# od2.net
KiCad netlist of a schematic drawn in EAGLE
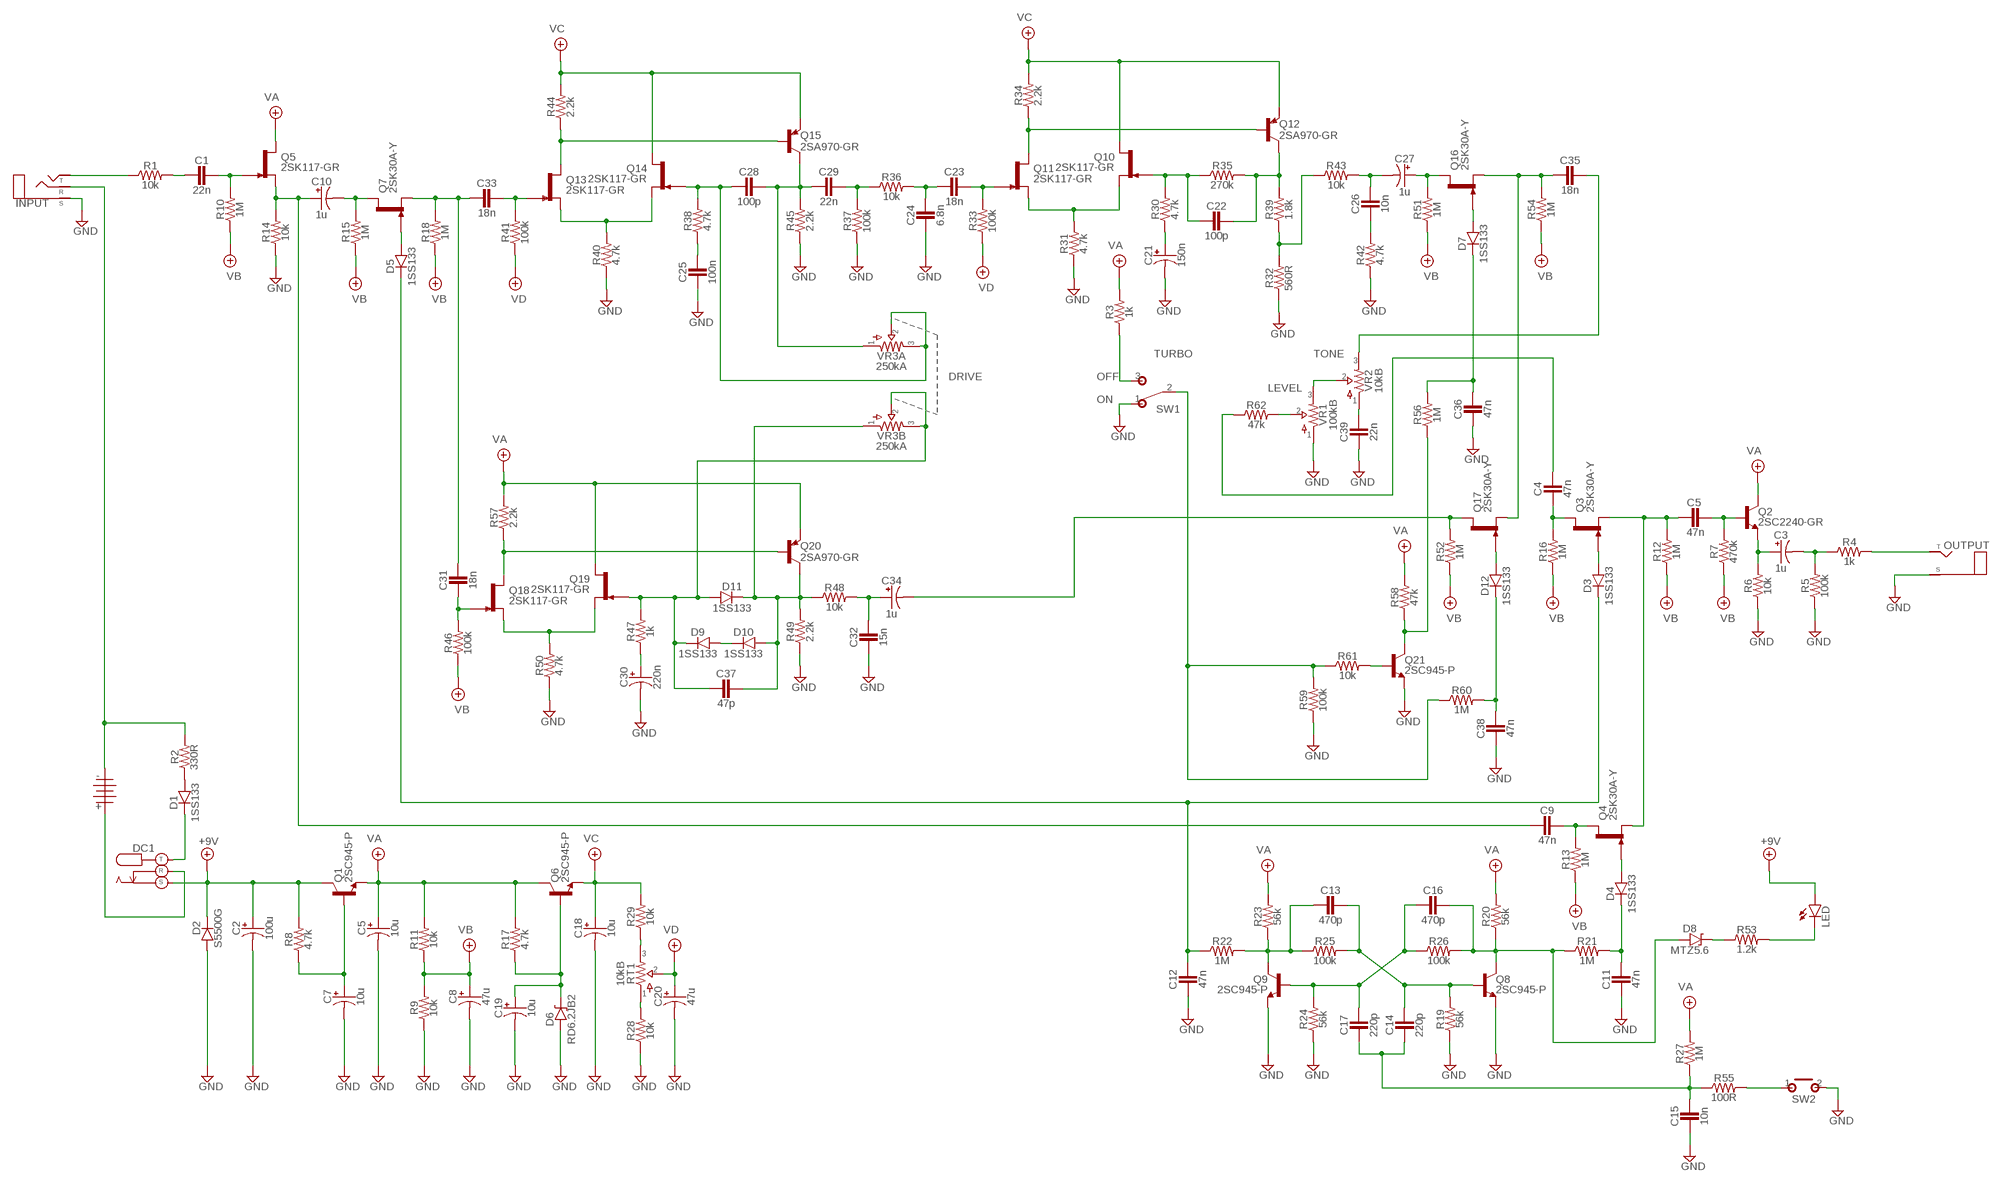
[diagram p0: schematic, sheet 1]

(export (version "E")
  (design (tool "Eeschema 10.0.6"))
  (components
    (comp (ref "11")
      (value "BATTERY")
      (footprint "eagle-import:TWO_PADS")
      (libsource (lib "eagle-import") (part "BATTERY"))
    )
    (comp (ref "C1")
      (value "22n")
      (footprint "eagle-import:BOX_SMALL")
      (libsource (lib "eagle-import") (part "CER/FILMBOX.1"))
    )
    (comp (ref "C2")
      (value "100u")
      (footprint "eagle-import:040_020")
      (libsource (lib "eagle-import") (part "0400"))
    )
    (comp (ref "C3")
      (value "1u")
      (footprint "eagle-import:040_020")
      (libsource (lib "eagle-import") (part "0400"))
    )
    (comp (ref "C4")
      (value "47n")
      (footprint "eagle-import:BOX_SMALL")
      (libsource (lib "eagle-import") (part "CER/FILMBOX.1"))
    )
    (comp (ref "C5")
      (value "10u")
      (footprint "eagle-import:040_020")
      (libsource (lib "eagle-import") (part "0400"))
    )
    (comp (ref "C5 ")
      (value "47n")
      (footprint "eagle-import:BOX_SMALL")
      (libsource (lib "eagle-import") (part "CER/FILMBOX.1"))
    )
    (comp (ref "C7")
      (value "10u")
      (footprint "eagle-import:040_020")
      (libsource (lib "eagle-import") (part "0400"))
    )
    (comp (ref "C8")
      (value "47u")
      (footprint "eagle-import:040_020")
      (libsource (lib "eagle-import") (part "0400"))
    )
    (comp (ref "C9")
      (value "47n")
      (footprint "eagle-import:BOX_SMALL")
      (libsource (lib "eagle-import") (part "CER/FILMBOX.1"))
    )
    (comp (ref "C10")
      (value "1u")
      (footprint "eagle-import:040_020")
      (libsource (lib "eagle-import") (part "0400"))
    )
    (comp (ref "C11")
      (value "47n")
      (footprint "eagle-import:BOX_SMALL")
      (libsource (lib "eagle-import") (part "CER/FILMBOX.1"))
    )
    (comp (ref "C12")
      (value "47n")
      (footprint "eagle-import:BOX_SMALL")
      (libsource (lib "eagle-import") (part "CER/FILMBOX.1"))
    )
    (comp (ref "C13")
      (value "470p")
      (footprint "eagle-import:BOX_SMALL")
      (libsource (lib "eagle-import") (part "CER/FILMBOX.1"))
    )
    (comp (ref "C14")
      (value "220p")
      (footprint "eagle-import:BOX_SMALL")
      (libsource (lib "eagle-import") (part "CER/FILMBOX.1"))
    )
    (comp (ref "C15")
      (value "10n")
      (footprint "eagle-import:BOX_SMALL")
      (libsource (lib "eagle-import") (part "CER/FILMBOX.1"))
    )
    (comp (ref "C16")
      (value "470p")
      (footprint "eagle-import:BOX_SMALL")
      (libsource (lib "eagle-import") (part "CER/FILMBOX.1"))
    )
    (comp (ref "C17")
      (value "220p")
      (footprint "eagle-import:BOX_SMALL")
      (libsource (lib "eagle-import") (part "CER/FILMBOX.1"))
    )
    (comp (ref "C18")
      (value "10u")
      (footprint "eagle-import:040_020")
      (libsource (lib "eagle-import") (part "0400"))
    )
    (comp (ref "C19")
      (value "10u")
      (footprint "eagle-import:040_020")
      (libsource (lib "eagle-import") (part "0400"))
    )
    (comp (ref "C20")
      (value "47u")
      (footprint "eagle-import:040_020")
      (libsource (lib "eagle-import") (part "0400"))
    )
    (comp (ref "C21")
      (value "150n")
      (footprint "eagle-import:040_020")
      (libsource (lib "eagle-import") (part "0400"))
    )
    (comp (ref "C22")
      (value "100p")
      (footprint "eagle-import:BOX_SMALL")
      (libsource (lib "eagle-import") (part "CER/FILMBOX.1"))
    )
    (comp (ref "C23")
      (value "18n")
      (footprint "eagle-import:BOX_SMALL")
      (libsource (lib "eagle-import") (part "CER/FILMBOX.1"))
    )
    (comp (ref "C24")
      (value "6.8n")
      (footprint "eagle-import:BOX_SMALL")
      (libsource (lib "eagle-import") (part "CER/FILMBOX.1"))
    )
    (comp (ref "C25")
      (value "100n")
      (footprint "eagle-import:BOX_SMALL")
      (libsource (lib "eagle-import") (part "CER/FILMBOX.1"))
    )
    (comp (ref "C26")
      (value "10n")
      (footprint "eagle-import:BOX_SMALL")
      (libsource (lib "eagle-import") (part "CER/FILMBOX.1"))
    )
    (comp (ref "C27")
      (value "1u")
      (footprint "eagle-import:040_020")
      (libsource (lib "eagle-import") (part "0400"))
    )
    (comp (ref "C28")
      (value "100p")
      (footprint "eagle-import:BOX_SMALL")
      (libsource (lib "eagle-import") (part "CER/FILMBOX.1"))
    )
    (comp (ref "C29")
      (value "22n")
      (footprint "eagle-import:BOX_SMALL")
      (libsource (lib "eagle-import") (part "CER/FILMBOX.1"))
    )
    (comp (ref "C30")
      (value "220n")
      (footprint "eagle-import:040_020")
      (libsource (lib "eagle-import") (part "0400"))
    )
    (comp (ref "C31")
      (value "18n")
      (footprint "eagle-import:BOX_SMALL")
      (libsource (lib "eagle-import") (part "CER/FILMBOX.1"))
    )
    (comp (ref "C32")
      (value "15n")
      (footprint "eagle-import:BOX_SMALL")
      (libsource (lib "eagle-import") (part "CER/FILMBOX.1"))
    )
    (comp (ref "C33")
      (value "18n")
      (footprint "eagle-import:BOX_SMALL")
      (libsource (lib "eagle-import") (part "CER/FILMBOX.1"))
    )
    (comp (ref "C34")
      (value "1u")
      (footprint "eagle-import:040_020")
      (libsource (lib "eagle-import") (part "0400"))
    )
    (comp (ref "C35")
      (value "18n")
      (footprint "eagle-import:BOX_SMALL")
      (libsource (lib "eagle-import") (part "CER/FILMBOX.1"))
    )
    (comp (ref "C36")
      (value "47n")
      (footprint "eagle-import:BOX_SMALL")
      (libsource (lib "eagle-import") (part "CER/FILMBOX.1"))
    )
    (comp (ref "C37")
      (value "47p")
      (footprint "eagle-import:BOX_SMALL")
      (libsource (lib "eagle-import") (part "CER/FILMBOX.1"))
    )
    (comp (ref "C38")
      (value "47n")
      (footprint "eagle-import:BOX_SMALL")
      (libsource (lib "eagle-import") (part "CER/FILMBOX.1"))
    )
    (comp (ref "C39")
      (value "22n")
      (footprint "eagle-import:BOX_SMALL")
      (libsource (lib "eagle-import") (part "CER/FILMBOX.1"))
    )
    (comp (ref "D1")
      (value "1SS133")
      (footprint "eagle-import:DO35-2")
      (libsource (lib "eagle-import") (part "DO35.2"))
    )
    (comp (ref "D2")
      (value "S5500G")
      (footprint "eagle-import:DO35-2")
      (libsource (lib "eagle-import") (part "DO35.2"))
    )
    (comp (ref "D3")
      (value "1SS133")
      (footprint "eagle-import:DO35-2")
      (libsource (lib "eagle-import") (part "DO35.2"))
    )
    (comp (ref "D4")
      (value "1SS133")
      (footprint "eagle-import:DO35-2")
      (libsource (lib "eagle-import") (part "DO35.2"))
    )
    (comp (ref "D5")
      (value "1SS133")
      (footprint "eagle-import:DO35-2")
      (libsource (lib "eagle-import") (part "DO35.2"))
    )
    (comp (ref "D6")
      (value "RD6.2JB2")
      (footprint "eagle-import:DO41-2")
      (libsource (lib "eagle-import") (part "ZENER.2"))
    )
    (comp (ref "D7")
      (value "1SS133")
      (footprint "eagle-import:DO35-2")
      (libsource (lib "eagle-import") (part "DO35.2"))
    )
    (comp (ref "D8")
      (value "MTZ5.6")
      (footprint "eagle-import:DO41-2")
      (libsource (lib "eagle-import") (part "ZENER.2"))
    )
    (comp (ref "D9")
      (value "1SS133")
      (footprint "eagle-import:DO35-2")
      (libsource (lib "eagle-import") (part "DO35.2"))
    )
    (comp (ref "D10")
      (value "1SS133")
      (footprint "eagle-import:DO35-2")
      (libsource (lib "eagle-import") (part "DO35.2"))
    )
    (comp (ref "D11")
      (value "1SS133")
      (footprint "eagle-import:DO35-2")
      (libsource (lib "eagle-import") (part "DO35.2"))
    )
    (comp (ref "D12")
      (value "1SS133")
      (footprint "eagle-import:DO35-2")
      (libsource (lib "eagle-import") (part "DO35.2"))
    )
    (comp (ref "DC1")
      (value "DC_KOBICONN")
      (footprint "eagle-import:DC_KOBICONN")
      (libsource (lib "eagle-import") (part "DC_KOBICONN"))
    )
    (comp (ref "INPUT")
      (value "STEREO3PADS")
      (footprint "eagle-import:THREEPADS")
      (libsource (lib "eagle-import") (part "STEREO3PADS"))
    )
    (comp (ref "LED")
      (value "LED")
      (footprint "eagle-import:3MM_D")
      (libsource (lib "eagle-import") (part "LED"))
    )
    (comp (ref "OUTPUT")
      (value "MONO")
      (footprint "eagle-import:TWO_PADS")
      (libsource (lib "eagle-import") (part "MONO"))
    )
    (comp (ref "Q1")
      (value "2SC945-P")
      (footprint "eagle-import:TO92-")
      (libsource (lib "eagle-import") (part "2SC828A"))
    )
    (comp (ref "Q2")
      (value "2SC2240-GR")
      (footprint "eagle-import:TO92-")
      (libsource (lib "eagle-import") (part "2SC828A"))
    )
    (comp (ref "Q3")
      (value "2SK30A-Y")
      (footprint "eagle-import:TO92-")
      (libsource (lib "eagle-import") (part "2N3819TO-92S"))
    )
    (comp (ref "Q4")
      (value "2SK30A-Y")
      (footprint "eagle-import:TO92-")
      (libsource (lib "eagle-import") (part "2N3819TO-92S"))
    )
    (comp (ref "Q5")
      (value "2SK117-GR")
      (footprint "eagle-import:TO92-")
      (libsource (lib "eagle-import") (part "2N3819TO-92S"))
    )
    (comp (ref "Q6")
      (value "2SC945-P")
      (footprint "eagle-import:TO92-")
      (libsource (lib "eagle-import") (part "2SC828A"))
    )
    (comp (ref "Q7")
      (value "2SK30A-Y")
      (footprint "eagle-import:TO92-")
      (libsource (lib "eagle-import") (part "2N3819TO-92S"))
    )
    (comp (ref "Q8")
      (value "2SC945-P")
      (footprint "eagle-import:TO92-")
      (libsource (lib "eagle-import") (part "2SC828A"))
    )
    (comp (ref "Q9")
      (value "2SC945-P")
      (footprint "eagle-import:TO92-")
      (libsource (lib "eagle-import") (part "2SC828A"))
    )
    (comp (ref "Q10")
      (value "2SK117-GR")
      (footprint "eagle-import:TO92-")
      (libsource (lib "eagle-import") (part "2N3819TO-92S"))
    )
    (comp (ref "Q11")
      (value "2SK117-GR")
      (footprint "eagle-import:TO92-")
      (libsource (lib "eagle-import") (part "2N3819TO-92S"))
    )
    (comp (ref "Q12")
      (value "2SA970-GR")
      (footprint "eagle-import:TO92")
      (libsource (lib "eagle-import") (part "2N3906"))
    )
    (comp (ref "Q13")
      (value "2SK117-GR")
      (footprint "eagle-import:TO92-")
      (libsource (lib "eagle-import") (part "2N3819TO-92S"))
    )
    (comp (ref "Q14")
      (value "2SK117-GR")
      (footprint "eagle-import:TO92-")
      (libsource (lib "eagle-import") (part "2N3819TO-92S"))
    )
    (comp (ref "Q15")
      (value "2SA970-GR")
      (footprint "eagle-import:TO92")
      (libsource (lib "eagle-import") (part "2N3906"))
    )
    (comp (ref "Q16")
      (value "2SK30A-Y")
      (footprint "eagle-import:TO92-")
      (libsource (lib "eagle-import") (part "2N3819TO-92S"))
    )
    (comp (ref "Q17")
      (value "2SK30A-Y")
      (footprint "eagle-import:TO92-")
      (libsource (lib "eagle-import") (part "2N3819TO-92S"))
    )
    (comp (ref "Q18")
      (value "2SK117-GR")
      (footprint "eagle-import:TO92-")
      (libsource (lib "eagle-import") (part "2N3819TO-92S"))
    )
    (comp (ref "Q19")
      (value "2SK117-GR")
      (footprint "eagle-import:TO92-")
      (libsource (lib "eagle-import") (part "2N3819TO-92S"))
    )
    (comp (ref "Q20")
      (value "2SA970-GR")
      (footprint "eagle-import:TO92")
      (libsource (lib "eagle-import") (part "2N3906"))
    )
    (comp (ref "Q21")
      (value "2SC945-P")
      (footprint "eagle-import:TO92-")
      (libsource (lib "eagle-import") (part "2SC828A"))
    )
    (comp (ref "R1")
      (value "10k")
      (footprint "eagle-import:R0207_3")
      (libsource (lib "eagle-import") (part "R_.3B"))
    )
    (comp (ref "R2")
      (value "330R")
      (footprint "eagle-import:R0207_3")
      (libsource (lib "eagle-import") (part "R_.3B"))
    )
    (comp (ref "R3")
      (value "1k")
      (footprint "eagle-import:R0207_3")
      (libsource (lib "eagle-import") (part "R_.3B"))
    )
    (comp (ref "R4")
      (value "1k")
      (footprint "eagle-import:R0207_3")
      (libsource (lib "eagle-import") (part "R_.3B"))
    )
    (comp (ref "R5")
      (value "100k")
      (footprint "eagle-import:R0207_3")
      (libsource (lib "eagle-import") (part "R_.3B"))
    )
    (comp (ref "R6")
      (value "10k")
      (footprint "eagle-import:R0207_3")
      (libsource (lib "eagle-import") (part "R_.3B"))
    )
    (comp (ref "R7")
      (value "470k")
      (footprint "eagle-import:R0207_3")
      (libsource (lib "eagle-import") (part "R_.3B"))
    )
    (comp (ref "R8")
      (value "4.7k")
      (footprint "eagle-import:R0207_3")
      (libsource (lib "eagle-import") (part "R_.3B"))
    )
    (comp (ref "R9")
      (value "10k")
      (footprint "eagle-import:R0207_3")
      (libsource (lib "eagle-import") (part "R_.3B"))
    )
    (comp (ref "R10")
      (value "1M")
      (footprint "eagle-import:R0207_3")
      (libsource (lib "eagle-import") (part "R_.3B"))
    )
    (comp (ref "R11")
      (value "10k")
      (footprint "eagle-import:R0207_3")
      (libsource (lib "eagle-import") (part "R_.3B"))
    )
    (comp (ref "R12")
      (value "1M")
      (footprint "eagle-import:R0207_3")
      (libsource (lib "eagle-import") (part "R_.3B"))
    )
    (comp (ref "R13")
      (value "1M")
      (footprint "eagle-import:R0207_3")
      (libsource (lib "eagle-import") (part "R_.3B"))
    )
    (comp (ref "R14")
      (value "10k")
      (footprint "eagle-import:R0207_3")
      (libsource (lib "eagle-import") (part "R_.3B"))
    )
    (comp (ref "R15")
      (value "1M")
      (footprint "eagle-import:R0207_3")
      (libsource (lib "eagle-import") (part "R_.3B"))
    )
    (comp (ref "R16")
      (value "1M")
      (footprint "eagle-import:R0207_3")
      (libsource (lib "eagle-import") (part "R_.3B"))
    )
    (comp (ref "R17")
      (value "4.7k")
      (footprint "eagle-import:R0207_3")
      (libsource (lib "eagle-import") (part "R_.3B"))
    )
    (comp (ref "R18")
      (value "1M")
      (footprint "eagle-import:R0207_3")
      (libsource (lib "eagle-import") (part "R_.3B"))
    )
    (comp (ref "R19")
      (value "56k")
      (footprint "eagle-import:R0207_3")
      (libsource (lib "eagle-import") (part "R_.3B"))
    )
    (comp (ref "R20")
      (value "56k")
      (footprint "eagle-import:R0207_3")
      (libsource (lib "eagle-import") (part "R_.3B"))
    )
    (comp (ref "R21")
      (value "1M")
      (footprint "eagle-import:R0207_3")
      (libsource (lib "eagle-import") (part "R_.3B"))
    )
    (comp (ref "R22")
      (value "1M")
      (footprint "eagle-import:R0207_3")
      (libsource (lib "eagle-import") (part "R_.3B"))
    )
    (comp (ref "R23")
      (value "56k")
      (footprint "eagle-import:R0207_3")
      (libsource (lib "eagle-import") (part "R_.3B"))
    )
    (comp (ref "R24")
      (value "56k")
      (footprint "eagle-import:R0207_3")
      (libsource (lib "eagle-import") (part "R_.3B"))
    )
    (comp (ref "R25")
      (value "100k")
      (footprint "eagle-import:R0207_3")
      (libsource (lib "eagle-import") (part "R_.3B"))
    )
    (comp (ref "R26")
      (value "100k")
      (footprint "eagle-import:R0207_3")
      (libsource (lib "eagle-import") (part "R_.3B"))
    )
    (comp (ref "R27")
      (value "1M")
      (footprint "eagle-import:R0207_3")
      (libsource (lib "eagle-import") (part "R_.3B"))
    )
    (comp (ref "R28")
      (value "10k")
      (footprint "eagle-import:R0207_3")
      (libsource (lib "eagle-import") (part "R_.3B"))
    )
    (comp (ref "R29")
      (value "10k")
      (footprint "eagle-import:R0207_3")
      (libsource (lib "eagle-import") (part "R_.3B"))
    )
    (comp (ref "R30")
      (value "4.7k")
      (footprint "eagle-import:R0207_3")
      (libsource (lib "eagle-import") (part "R_.3B"))
    )
    (comp (ref "R31")
      (value "4.7k")
      (footprint "eagle-import:R0207_3")
      (libsource (lib "eagle-import") (part "R_.3B"))
    )
    (comp (ref "R32")
      (value "560R")
      (footprint "eagle-import:R0207_3")
      (libsource (lib "eagle-import") (part "R_.3B"))
    )
    (comp (ref "R33")
      (value "100k")
      (footprint "eagle-import:R0207_3")
      (libsource (lib "eagle-import") (part "R_.3B"))
    )
    (comp (ref "R34")
      (value "2.2k")
      (footprint "eagle-import:R0207_3")
      (libsource (lib "eagle-import") (part "R_.3B"))
    )
    (comp (ref "R35")
      (value "270k")
      (footprint "eagle-import:R0207_3")
      (libsource (lib "eagle-import") (part "R_.3B"))
    )
    (comp (ref "R36")
      (value "10k")
      (footprint "eagle-import:R0207_3")
      (libsource (lib "eagle-import") (part "R_.3B"))
    )
    (comp (ref "R37")
      (value "100k")
      (footprint "eagle-import:R0207_3")
      (libsource (lib "eagle-import") (part "R_.3B"))
    )
    (comp (ref "R38")
      (value "4.7k")
      (footprint "eagle-import:R0207_3")
      (libsource (lib "eagle-import") (part "R_.3B"))
    )
    (comp (ref "R39")
      (value "1.8k")
      (footprint "eagle-import:R0207_3")
      (libsource (lib "eagle-import") (part "R_.3B"))
    )
    (comp (ref "R40")
      (value "4.7k")
      (footprint "eagle-import:R0207_3")
      (libsource (lib "eagle-import") (part "R_.3B"))
    )
    (comp (ref "R41")
      (value "100k")
      (footprint "eagle-import:R0207_3")
      (libsource (lib "eagle-import") (part "R_.3B"))
    )
    (comp (ref "R42")
      (value "4.7k")
      (footprint "eagle-import:R0207_3")
      (libsource (lib "eagle-import") (part "R_.3B"))
    )
    (comp (ref "R43")
      (value "10k")
      (footprint "eagle-import:R0207_3")
      (libsource (lib "eagle-import") (part "R_.3B"))
    )
    (comp (ref "R44")
      (value "2.2k")
      (footprint "eagle-import:R0207_3")
      (libsource (lib "eagle-import") (part "R_.3B"))
    )
    (comp (ref "R45")
      (value "2.2k")
      (footprint "eagle-import:R0207_3")
      (libsource (lib "eagle-import") (part "R_.3B"))
    )
    (comp (ref "R46")
      (value "100k")
      (footprint "eagle-import:R0207_3")
      (libsource (lib "eagle-import") (part "R_.3B"))
    )
    (comp (ref "R47")
      (value "1k")
      (footprint "eagle-import:R0207_3")
      (libsource (lib "eagle-import") (part "R_.3B"))
    )
    (comp (ref "R48")
      (value "10k")
      (footprint "eagle-import:R0207_3")
      (libsource (lib "eagle-import") (part "R_.3B"))
    )
    (comp (ref "R49")
      (value "2.2k")
      (footprint "eagle-import:R0207_3")
      (libsource (lib "eagle-import") (part "R_.3B"))
    )
    (comp (ref "R50")
      (value "4.7k")
      (footprint "eagle-import:R0207_3")
      (libsource (lib "eagle-import") (part "R_.3B"))
    )
    (comp (ref "R51")
      (value "1M")
      (footprint "eagle-import:R0207_3")
      (libsource (lib "eagle-import") (part "R_.3B"))
    )
    (comp (ref "R52")
      (value "1M")
      (footprint "eagle-import:R0207_3")
      (libsource (lib "eagle-import") (part "R_.3B"))
    )
    (comp (ref "R53")
      (value "1.2k")
      (footprint "eagle-import:R0207_3")
      (libsource (lib "eagle-import") (part "R_.3B"))
    )
    (comp (ref "R54")
      (value "1M")
      (footprint "eagle-import:R0207_3")
      (libsource (lib "eagle-import") (part "R_.3B"))
    )
    (comp (ref "R55")
      (value "100R")
      (footprint "eagle-import:R0207_3")
      (libsource (lib "eagle-import") (part "R_.3B"))
    )
    (comp (ref "R56")
      (value "1M")
      (footprint "eagle-import:R0207_3")
      (libsource (lib "eagle-import") (part "R_.3B"))
    )
    (comp (ref "R57")
      (value "2.2k")
      (footprint "eagle-import:R0207_3")
      (libsource (lib "eagle-import") (part "R_.3B"))
    )
    (comp (ref "R58")
      (value "47k")
      (footprint "eagle-import:R0207_3")
      (libsource (lib "eagle-import") (part "R_.3B"))
    )
    (comp (ref "R59")
      (value "100k")
      (footprint "eagle-import:R0207_3")
      (libsource (lib "eagle-import") (part "R_.3B"))
    )
    (comp (ref "R60")
      (value "1M")
      (footprint "eagle-import:R0207_3")
      (libsource (lib "eagle-import") (part "R_.3B"))
    )
    (comp (ref "R61")
      (value "10k")
      (footprint "eagle-import:R0207_3")
      (libsource (lib "eagle-import") (part "R_.3B"))
    )
    (comp (ref "R62")
      (value "47k")
      (footprint "eagle-import:R0207_3")
      (libsource (lib "eagle-import") (part "R_.3B"))
    )
    (comp (ref "RT1")
      (value "10kB")
      (footprint "eagle-import:16MM")
      (libsource (lib "eagle-import") (part "POTS16MM"))
    )
    (comp (ref "SW1")
      (value "SPDT")
      (footprint "eagle-import:M9040P")
      (libsource (lib "eagle-import") (part "SPDT"))
    )
    (comp (ref "SW2")
      (value "MOMENTARY")
      (footprint "eagle-import:SPST")
      (libsource (lib "eagle-import") (part "MOMENTARY"))
    )
    (comp (ref "VR1")
      (value "100kB")
      (footprint "eagle-import:16MM")
      (libsource (lib "eagle-import") (part "POTS16MM"))
    )
    (comp (ref "VR2")
      (value "10kB")
      (footprint "eagle-import:16MM")
      (libsource (lib "eagle-import") (part "POTS16MM"))
    )
    (comp (ref "VR3A")
      (value "250kA")
      (footprint "eagle-import:16MM")
      (libsource (lib "eagle-import") (part "POTS16MM"))
    )
    (comp (ref "VR3B")
      (value "250kA")
      (footprint "eagle-import:16MM")
      (libsource (lib "eagle-import") (part "POTS16MM"))
    )
  )
  (nets
    (net (code "1") (name "+9V") (class "Default")
      (node (ref "C2") (pin "+") (pinfunction "+_+") (pintype "passive"))
      (node (ref "D2") (pin "C") (pinfunction "C_C") (pintype "passive"))
      (node (ref "DC1") (pin "S") (pinfunction "S_S") (pintype "bidirectional"))
      (node (ref "LED") (pin "ANODE") (pinfunction "A_ANODE") (pintype "passive"))
      (node (ref "Q1") (pin "2") (pinfunction "C_2") (pintype "passive"))
      (node (ref "R8") (pin "2") (pinfunction "2_2") (pintype "passive"))
    )
    (net (code "2") (name "GND") (class "Default")
      (node (ref "C11") (pin "2") (pinfunction "2_2") (pintype "passive"))
      (node (ref "C12") (pin "2") (pinfunction "2_2") (pintype "passive"))
      (node (ref "C15") (pin "2") (pinfunction "2_2") (pintype "passive"))
      (node (ref "C18") (pin "-") (pinfunction "-_-") (pintype "passive"))
      (node (ref "C19") (pin "-") (pinfunction "-_-") (pintype "passive"))
      (node (ref "C2") (pin "-") (pinfunction "-_-") (pintype "passive"))
      (node (ref "C20") (pin "-") (pinfunction "-_-") (pintype "passive"))
      (node (ref "C21") (pin "-") (pinfunction "-_-") (pintype "passive"))
      (node (ref "C24") (pin "2") (pinfunction "2_2") (pintype "passive"))
      (node (ref "C25") (pin "2") (pinfunction "2_2") (pintype "passive"))
      (node (ref "C30") (pin "-") (pinfunction "-_-") (pintype "passive"))
      (node (ref "C32") (pin "2") (pinfunction "2_2") (pintype "passive"))
      (node (ref "C36") (pin "2") (pinfunction "2_2") (pintype "passive"))
      (node (ref "C38") (pin "2") (pinfunction "2_2") (pintype "passive"))
      (node (ref "C39") (pin "2") (pinfunction "2_2") (pintype "passive"))
      (node (ref "C5") (pin "-") (pinfunction "-_-") (pintype "passive"))
      (node (ref "C7") (pin "-") (pinfunction "-_-") (pintype "passive"))
      (node (ref "C8") (pin "-") (pinfunction "-_-") (pintype "passive"))
      (node (ref "D2") (pin "A") (pinfunction "A_A") (pintype "passive"))
      (node (ref "D6") (pin "A") (pinfunction "A_A") (pintype "passive"))
      (node (ref "INPUT") (pin "SLEEVE") (pinfunction "S_SLEEVE") (pintype "passive"))
      (node (ref "OUTPUT") (pin "S") (pinfunction "SLEEVE_S") (pintype "passive"))
      (node (ref "Q21") (pin "3") (pinfunction "E_3") (pintype "passive"))
      (node (ref "Q8") (pin "3") (pinfunction "E_3") (pintype "passive"))
      (node (ref "Q9") (pin "3") (pinfunction "E_3") (pintype "passive"))
      (node (ref "R14") (pin "1") (pinfunction "1_1") (pintype "passive"))
      (node (ref "R19") (pin "1") (pinfunction "1_1") (pintype "passive"))
      (node (ref "R24") (pin "1") (pinfunction "1_1") (pintype "passive"))
      (node (ref "R28") (pin "1") (pinfunction "1_1") (pintype "passive"))
      (node (ref "R31") (pin "1") (pinfunction "1_1") (pintype "passive"))
      (node (ref "R32") (pin "1") (pinfunction "1_1") (pintype "passive"))
      (node (ref "R37") (pin "1") (pinfunction "1_1") (pintype "passive"))
      (node (ref "R40") (pin "1") (pinfunction "1_1") (pintype "passive"))
      (node (ref "R42") (pin "1") (pinfunction "1_1") (pintype "passive"))
      (node (ref "R45") (pin "1") (pinfunction "1_1") (pintype "passive"))
      (node (ref "R49") (pin "1") (pinfunction "1_1") (pintype "passive"))
      (node (ref "R5") (pin "1") (pinfunction "1_1") (pintype "passive"))
      (node (ref "R50") (pin "1") (pinfunction "1_1") (pintype "passive"))
      (node (ref "R59") (pin "1") (pinfunction "1_1") (pintype "passive"))
      (node (ref "R6") (pin "1") (pinfunction "1_1") (pintype "passive"))
      (node (ref "R9") (pin "1") (pinfunction "1_1") (pintype "passive"))
      (node (ref "SW1") (pin "1") (pinfunction "O_1") (pintype "passive"))
      (node (ref "SW2") (pin "2") (pinfunction "S_2") (pintype "passive"))
      (node (ref "VR1") (pin "1") (pinfunction "1_1") (pintype "passive"))
    )
    (net (code "3") (name "Net-(11-P$1)") (class "Default")
      (node (ref "11") (pin "T") (pinfunction "P$1_T") (pintype "bidirectional"))
      (node (ref "DC1") (pin "R") (pinfunction "R_R") (pintype "bidirectional"))
    )
    (net (code "4") (name "Net-(11-P$2)") (class "Default")
      (node (ref "11") (pin "S") (pinfunction "P$2_S") (pintype "bidirectional"))
      (node (ref "INPUT") (pin "RING") (pinfunction "R_RING") (pintype "passive"))
      (node (ref "R2") (pin "2") (pinfunction "2_2") (pintype "passive"))
    )
    (net (code "5") (name "Net-(C1-Pad2)") (class "Default")
      (node (ref "C1") (pin "2") (pinfunction "2_2") (pintype "passive"))
      (node (ref "R1") (pin "2") (pinfunction "2_2") (pintype "passive"))
    )
    (net (code "6") (name "Net-(C3-Pad-)") (class "Default")
      (node (ref "C3") (pin "-") (pinfunction "-_-") (pintype "passive"))
      (node (ref "R4") (pin "1") (pinfunction "1_1") (pintype "passive"))
      (node (ref "R5") (pin "2") (pinfunction "2_2") (pintype "passive"))
    )
    (net (code "7") (name "Net-(C4-Pad1)") (class "Default")
      (node (ref "C4") (pin "1") (pinfunction "1_1") (pintype "passive"))
      (node (ref "R62") (pin "1") (pinfunction "1_1") (pintype "passive"))
    )
    (net (code "8") (name "Net-(C11-Pad1)") (class "Default")
      (node (ref "C11") (pin "1") (pinfunction "1_1") (pintype "passive"))
      (node (ref "D4") (pin "C") (pinfunction "C_C") (pintype "passive"))
      (node (ref "R21") (pin "2") (pinfunction "2_2") (pintype "passive"))
    )
    (net (code "9") (name "Net-(C12-Pad1)") (class "Default")
      (node (ref "C12") (pin "1") (pinfunction "1_1") (pintype "passive"))
      (node (ref "D3") (pin "C") (pinfunction "C_C") (pintype "passive"))
      (node (ref "D5") (pin "C") (pinfunction "C_C") (pintype "passive"))
      (node (ref "R22") (pin "1") (pinfunction "1_1") (pintype "passive"))
    )
    (net (code "10") (name "Net-(C14-Pad2)") (class "Default")
      (node (ref "C14") (pin "2") (pinfunction "2_2") (pintype "passive"))
      (node (ref "C15") (pin "1") (pinfunction "1_1") (pintype "passive"))
      (node (ref "C17") (pin "2") (pinfunction "2_2") (pintype "passive"))
      (node (ref "R27") (pin "1") (pinfunction "1_1") (pintype "passive"))
      (node (ref "R55") (pin "1") (pinfunction "1_1") (pintype "passive"))
    )
    (net (code "11") (name "Net-(C21-Pad+)") (class "Default")
      (node (ref "C21") (pin "+") (pinfunction "+_+") (pintype "passive"))
      (node (ref "R30") (pin "1") (pinfunction "1_1") (pintype "passive"))
    )
    (net (code "12") (name "Net-(C23-Pad2)") (class "Default")
      (node (ref "C23") (pin "2") (pinfunction "2_2") (pintype "passive"))
      (node (ref "C24") (pin "1") (pinfunction "1_1") (pintype "passive"))
      (node (ref "R36") (pin "2") (pinfunction "2_2") (pintype "passive"))
    )
    (net (code "13") (name "Net-(C25-Pad1)") (class "Default")
      (node (ref "C25") (pin "1") (pinfunction "1_1") (pintype "passive"))
      (node (ref "R38") (pin "1") (pinfunction "1_1") (pintype "passive"))
    )
    (net (code "14") (name "Net-(C26-Pad1)") (class "Default")
      (node (ref "C26") (pin "1") (pinfunction "1_1") (pintype "passive"))
      (node (ref "C27") (pin "-") (pinfunction "-_-") (pintype "passive"))
      (node (ref "R43") (pin "2") (pinfunction "2_2") (pintype "passive"))
    )
    (net (code "15") (name "Net-(C26-Pad2)") (class "Default")
      (node (ref "C26") (pin "2") (pinfunction "2_2") (pintype "passive"))
      (node (ref "R42") (pin "2") (pinfunction "2_2") (pintype "passive"))
    )
    (net (code "16") (name "Net-(C29-Pad1)") (class "Default")
      (node (ref "C29") (pin "1") (pinfunction "1_1") (pintype "passive"))
      (node (ref "R36") (pin "1") (pinfunction "1_1") (pintype "passive"))
      (node (ref "R37") (pin "2") (pinfunction "2_2") (pintype "passive"))
    )
    (net (code "17") (name "Net-(C30-Pad+)") (class "Default")
      (node (ref "C30") (pin "+") (pinfunction "+_+") (pintype "passive"))
      (node (ref "R47") (pin "1") (pinfunction "1_1") (pintype "passive"))
    )
    (net (code "18") (name "Net-(C32-Pad1)") (class "Default")
      (node (ref "C32") (pin "1") (pinfunction "1_1") (pintype "passive"))
      (node (ref "C34") (pin "+") (pinfunction "+_+") (pintype "passive"))
      (node (ref "R48") (pin "2") (pinfunction "2_2") (pintype "passive"))
    )
    (net (code "19") (name "Net-(C35-Pad1)") (class "Default")
      (node (ref "C35") (pin "1") (pinfunction "1_1") (pintype "passive"))
      (node (ref "VR2") (pin "3") (pinfunction "3_3") (pintype "passive"))
    )
    (net (code "20") (name "Net-(C36-Pad1)") (class "Default")
      (node (ref "C36") (pin "1") (pinfunction "1_1") (pintype "passive"))
      (node (ref "D7") (pin "C") (pinfunction "C_C") (pintype "passive"))
      (node (ref "R56") (pin "2") (pinfunction "2_2") (pintype "passive"))
    )
    (net (code "21") (name "Net-(C38-Pad1)") (class "Default")
      (node (ref "C38") (pin "1") (pinfunction "1_1") (pintype "passive"))
      (node (ref "D12") (pin "C") (pinfunction "C_C") (pintype "passive"))
      (node (ref "R60") (pin "2") (pinfunction "2_2") (pintype "passive"))
    )
    (net (code "22") (name "Net-(C39-Pad1)") (class "Default")
      (node (ref "C39") (pin "1") (pinfunction "1_1") (pintype "passive"))
      (node (ref "VR2") (pin "1") (pinfunction "1_1") (pintype "passive"))
    )
    (net (code "23") (name "Net-(D1-PadA)") (class "Default")
      (node (ref "D1") (pin "A") (pinfunction "A_A") (pintype "passive"))
      (node (ref "R2") (pin "1") (pinfunction "1_1") (pintype "passive"))
    )
    (net (code "24") (name "Net-(D1-PadC)") (class "Default")
      (node (ref "D1") (pin "C") (pinfunction "C_C") (pintype "passive"))
      (node (ref "DC1") (pin "T") (pinfunction "T_T") (pintype "bidirectional"))
    )
    (net (code "25") (name "Net-(D8-PadC)") (class "Default")
      (node (ref "D8") (pin "C") (pinfunction "C_C") (pintype "passive"))
      (node (ref "R53") (pin "1") (pinfunction "1_1") (pintype "passive"))
    )
    (net (code "26") (name "Net-(D10-PadC)") (class "Default")
      (node (ref "D10") (pin "C") (pinfunction "C_C") (pintype "passive"))
      (node (ref "D9") (pin "A") (pinfunction "A_A") (pintype "passive"))
    )
    (net (code "27") (name "Net-(INPUT-T)") (class "Default")
      (node (ref "INPUT") (pin "TIP") (pinfunction "T_TIP") (pintype "passive"))
      (node (ref "R1") (pin "1") (pinfunction "1_1") (pintype "passive"))
    )
    (net (code "28") (name "Net-(LED-C)") (class "Default")
      (node (ref "LED") (pin "P$1") (pinfunction "C_P$1") (pintype "passive"))
      (node (ref "R53") (pin "2") (pinfunction "2_2") (pintype "passive"))
    )
    (net (code "29") (name "Net-(OUTPUT-TIP)") (class "Default")
      (node (ref "OUTPUT") (pin "T") (pinfunction "TIP_T") (pintype "passive"))
      (node (ref "R4") (pin "2") (pinfunction "2_2") (pintype "passive"))
    )
    (net (code "30") (name "Net-(Q1-B)") (class "Default")
      (node (ref "C7") (pin "+") (pinfunction "+_+") (pintype "passive"))
      (node (ref "Q1") (pin "1") (pinfunction "B_1") (pintype "passive"))
      (node (ref "R8") (pin "1") (pinfunction "1_1") (pintype "passive"))
    )
    (net (code "31") (name "Net-(Q2-B)") (class "Default")
      (node (ref "C5 ") (pin "1") (pinfunction "1_1") (pintype "passive"))
      (node (ref "Q2") (pin "1") (pinfunction "B_1") (pintype "passive"))
      (node (ref "R7") (pin "2") (pinfunction "2_2") (pintype "passive"))
    )
    (net (code "32") (name "Net-(Q2-E)") (class "Default")
      (node (ref "C3") (pin "+") (pinfunction "+_+") (pintype "passive"))
      (node (ref "Q2") (pin "3") (pinfunction "E_3") (pintype "passive"))
      (node (ref "R6") (pin "2") (pinfunction "2_2") (pintype "passive"))
    )
    (net (code "33") (name "Net-(Q3-D)") (class "Default")
      (node (ref "C4") (pin "2") (pinfunction "2_2") (pintype "passive"))
      (node (ref "Q3") (pin "3") (pinfunction "D_3") (pintype "passive"))
      (node (ref "R16") (pin "2") (pinfunction "2_2") (pintype "passive"))
    )
    (net (code "34") (name "Net-(Q3-G)") (class "Default")
      (node (ref "D3") (pin "A") (pinfunction "A_A") (pintype "passive"))
      (node (ref "Q3") (pin "2") (pinfunction "G_2") (pintype "passive"))
    )
    (net (code "35") (name "Net-(Q3-S)") (class "Default")
      (node (ref "C5 ") (pin "2") (pinfunction "2_2") (pintype "passive"))
      (node (ref "Q3") (pin "1") (pinfunction "S_1") (pintype "passive"))
      (node (ref "Q4") (pin "1") (pinfunction "S_1") (pintype "passive"))
      (node (ref "R12") (pin "2") (pinfunction "2_2") (pintype "passive"))
    )
    (net (code "36") (name "Net-(Q4-D)") (class "Default")
      (node (ref "C9") (pin "1") (pinfunction "1_1") (pintype "passive"))
      (node (ref "Q4") (pin "3") (pinfunction "D_3") (pintype "passive"))
      (node (ref "R13") (pin "2") (pinfunction "2_2") (pintype "passive"))
    )
    (net (code "37") (name "Net-(Q4-G)") (class "Default")
      (node (ref "D4") (pin "A") (pinfunction "A_A") (pintype "passive"))
      (node (ref "Q4") (pin "2") (pinfunction "G_2") (pintype "passive"))
    )
    (net (code "38") (name "Net-(Q5-G)") (class "Default")
      (node (ref "C1") (pin "1") (pinfunction "1_1") (pintype "passive"))
      (node (ref "Q5") (pin "2") (pinfunction "G_2") (pintype "passive"))
      (node (ref "R10") (pin "2") (pinfunction "2_2") (pintype "passive"))
    )
    (net (code "39") (name "Net-(Q5-S)") (class "Default")
      (node (ref "C10") (pin "+") (pinfunction "+_+") (pintype "passive"))
      (node (ref "C9") (pin "2") (pinfunction "2_2") (pintype "passive"))
      (node (ref "Q5") (pin "1") (pinfunction "S_1") (pintype "passive"))
      (node (ref "R14") (pin "2") (pinfunction "2_2") (pintype "passive"))
    )
    (net (code "40") (name "Net-(Q6-B)") (class "Default")
      (node (ref "C19") (pin "+") (pinfunction "+_+") (pintype "passive"))
      (node (ref "D6") (pin "C") (pinfunction "C_C") (pintype "passive"))
      (node (ref "Q6") (pin "1") (pinfunction "B_1") (pintype "passive"))
      (node (ref "R17") (pin "1") (pinfunction "1_1") (pintype "passive"))
    )
    (net (code "41") (name "Net-(Q7-D)") (class "Default")
      (node (ref "C10") (pin "-") (pinfunction "-_-") (pintype "passive"))
      (node (ref "Q7") (pin "3") (pinfunction "D_3") (pintype "passive"))
      (node (ref "R15") (pin "2") (pinfunction "2_2") (pintype "passive"))
    )
    (net (code "42") (name "Net-(Q7-G)") (class "Default")
      (node (ref "D5") (pin "A") (pinfunction "A_A") (pintype "passive"))
      (node (ref "Q7") (pin "2") (pinfunction "G_2") (pintype "passive"))
    )
    (net (code "43") (name "Net-(Q7-S)") (class "Default")
      (node (ref "C31") (pin "1") (pinfunction "1_1") (pintype "passive"))
      (node (ref "C33") (pin "2") (pinfunction "2_2") (pintype "passive"))
      (node (ref "Q7") (pin "1") (pinfunction "S_1") (pintype "passive"))
      (node (ref "R18") (pin "2") (pinfunction "2_2") (pintype "passive"))
    )
    (net (code "44") (name "Net-(Q8-B)") (class "Default")
      (node (ref "C13") (pin "1") (pinfunction "1_1") (pintype "passive"))
      (node (ref "C14") (pin "1") (pinfunction "1_1") (pintype "passive"))
      (node (ref "Q8") (pin "1") (pinfunction "B_1") (pintype "passive"))
      (node (ref "R19") (pin "2") (pinfunction "2_2") (pintype "passive"))
      (node (ref "R25") (pin "2") (pinfunction "2_2") (pintype "passive"))
    )
    (net (code "45") (name "Net-(Q8-C)") (class "Default")
      (node (ref "C16") (pin "1") (pinfunction "1_1") (pintype "passive"))
      (node (ref "D8") (pin "A") (pinfunction "A_A") (pintype "passive"))
      (node (ref "Q8") (pin "2") (pinfunction "C_2") (pintype "passive"))
      (node (ref "R20") (pin "1") (pinfunction "1_1") (pintype "passive"))
      (node (ref "R21") (pin "1") (pinfunction "1_1") (pintype "passive"))
      (node (ref "R26") (pin "2") (pinfunction "2_2") (pintype "passive"))
    )
    (net (code "46") (name "Net-(Q9-B)") (class "Default")
      (node (ref "C16") (pin "2") (pinfunction "2_2") (pintype "passive"))
      (node (ref "C17") (pin "1") (pinfunction "1_1") (pintype "passive"))
      (node (ref "Q9") (pin "1") (pinfunction "B_1") (pintype "passive"))
      (node (ref "R24") (pin "2") (pinfunction "2_2") (pintype "passive"))
      (node (ref "R26") (pin "1") (pinfunction "1_1") (pintype "passive"))
    )
    (net (code "47") (name "Net-(Q9-C)") (class "Default")
      (node (ref "C13") (pin "2") (pinfunction "2_2") (pintype "passive"))
      (node (ref "Q9") (pin "2") (pinfunction "C_2") (pintype "passive"))
      (node (ref "R22") (pin "2") (pinfunction "2_2") (pintype "passive"))
      (node (ref "R23") (pin "1") (pinfunction "1_1") (pintype "passive"))
      (node (ref "R25") (pin "1") (pinfunction "1_1") (pintype "passive"))
    )
    (net (code "48") (name "Net-(Q10-G)") (class "Default")
      (node (ref "C22") (pin "2") (pinfunction "2_2") (pintype "passive"))
      (node (ref "Q10") (pin "2") (pinfunction "G_2") (pintype "passive"))
      (node (ref "R30") (pin "2") (pinfunction "2_2") (pintype "passive"))
      (node (ref "R35") (pin "1") (pinfunction "1_1") (pintype "passive"))
    )
    (net (code "49") (name "Net-(Q10-S)") (class "Default")
      (node (ref "Q10") (pin "1") (pinfunction "S_1") (pintype "passive"))
      (node (ref "Q11") (pin "1") (pinfunction "S_1") (pintype "passive"))
      (node (ref "R31") (pin "2") (pinfunction "2_2") (pintype "passive"))
    )
    (net (code "50") (name "Net-(Q11-D)") (class "Default")
      (node (ref "Q11") (pin "3") (pinfunction "D_3") (pintype "passive"))
      (node (ref "Q12") (pin "2") (pinfunction "B_2") (pintype "passive"))
      (node (ref "R34") (pin "1") (pinfunction "1_1") (pintype "passive"))
    )
    (net (code "51") (name "Net-(Q11-G)") (class "Default")
      (node (ref "C23") (pin "1") (pinfunction "1_1") (pintype "passive"))
      (node (ref "Q11") (pin "2") (pinfunction "G_2") (pintype "passive"))
      (node (ref "R33") (pin "2") (pinfunction "2_2") (pintype "passive"))
    )
    (net (code "52") (name "Net-(Q12-C)") (class "Default")
      (node (ref "C22") (pin "1") (pinfunction "1_1") (pintype "passive"))
      (node (ref "Q12") (pin "1") (pinfunction "C_1") (pintype "passive"))
      (node (ref "R35") (pin "2") (pinfunction "2_2") (pintype "passive"))
      (node (ref "R39") (pin "2") (pinfunction "2_2") (pintype "passive"))
    )
    (net (code "53") (name "Net-(Q13-D)") (class "Default")
      (node (ref "Q13") (pin "3") (pinfunction "D_3") (pintype "passive"))
      (node (ref "Q15") (pin "2") (pinfunction "B_2") (pintype "passive"))
      (node (ref "R44") (pin "1") (pinfunction "1_1") (pintype "passive"))
    )
    (net (code "54") (name "Net-(Q13-G)") (class "Default")
      (node (ref "C33") (pin "1") (pinfunction "1_1") (pintype "passive"))
      (node (ref "Q13") (pin "2") (pinfunction "G_2") (pintype "passive"))
      (node (ref "R41") (pin "2") (pinfunction "2_2") (pintype "passive"))
    )
    (net (code "55") (name "Net-(Q13-S)") (class "Default")
      (node (ref "Q13") (pin "1") (pinfunction "S_1") (pintype "passive"))
      (node (ref "Q14") (pin "1") (pinfunction "S_1") (pintype "passive"))
      (node (ref "R40") (pin "2") (pinfunction "2_2") (pintype "passive"))
    )
    (net (code "56") (name "Net-(Q14-G)") (class "Default")
      (node (ref "C28") (pin "2") (pinfunction "2_2") (pintype "passive"))
      (node (ref "Q14") (pin "2") (pinfunction "G_2") (pintype "passive"))
      (node (ref "R38") (pin "2") (pinfunction "2_2") (pintype "passive"))
      (node (ref "VR3A") (pin "2") (pinfunction "2_2") (pintype "passive"))
      (node (ref "VR3A") (pin "3") (pinfunction "3_3") (pintype "passive"))
    )
    (net (code "57") (name "Net-(Q15-C)") (class "Default")
      (node (ref "C28") (pin "1") (pinfunction "1_1") (pintype "passive"))
      (node (ref "C29") (pin "2") (pinfunction "2_2") (pintype "passive"))
      (node (ref "Q15") (pin "1") (pinfunction "C_1") (pintype "passive"))
      (node (ref "R45") (pin "2") (pinfunction "2_2") (pintype "passive"))
      (node (ref "VR3A") (pin "1") (pinfunction "1_1") (pintype "passive"))
    )
    (net (code "58") (name "Net-(Q16-D)") (class "Default")
      (node (ref "C27") (pin "+") (pinfunction "+_+") (pintype "passive"))
      (node (ref "Q16") (pin "3") (pinfunction "D_3") (pintype "passive"))
      (node (ref "R51") (pin "2") (pinfunction "2_2") (pintype "passive"))
    )
    (net (code "59") (name "Net-(Q16-G)") (class "Default")
      (node (ref "D7") (pin "A") (pinfunction "A_A") (pintype "passive"))
      (node (ref "Q16") (pin "2") (pinfunction "G_2") (pintype "passive"))
    )
    (net (code "60") (name "Net-(Q16-S)") (class "Default")
      (node (ref "C35") (pin "2") (pinfunction "2_2") (pintype "passive"))
      (node (ref "Q16") (pin "1") (pinfunction "S_1") (pintype "passive"))
      (node (ref "Q17") (pin "1") (pinfunction "S_1") (pintype "passive"))
      (node (ref "R54") (pin "2") (pinfunction "2_2") (pintype "passive"))
    )
    (net (code "61") (name "Net-(Q17-D)") (class "Default")
      (node (ref "C34") (pin "-") (pinfunction "-_-") (pintype "passive"))
      (node (ref "Q17") (pin "3") (pinfunction "D_3") (pintype "passive"))
      (node (ref "R52") (pin "2") (pinfunction "2_2") (pintype "passive"))
    )
    (net (code "62") (name "Net-(Q17-G)") (class "Default")
      (node (ref "D12") (pin "A") (pinfunction "A_A") (pintype "passive"))
      (node (ref "Q17") (pin "2") (pinfunction "G_2") (pintype "passive"))
    )
    (net (code "63") (name "Net-(Q18-D)") (class "Default")
      (node (ref "Q18") (pin "3") (pinfunction "D_3") (pintype "passive"))
      (node (ref "Q20") (pin "2") (pinfunction "B_2") (pintype "passive"))
      (node (ref "R57") (pin "1") (pinfunction "1_1") (pintype "passive"))
    )
    (net (code "64") (name "Net-(Q18-G)") (class "Default")
      (node (ref "C31") (pin "2") (pinfunction "2_2") (pintype "passive"))
      (node (ref "Q18") (pin "2") (pinfunction "G_2") (pintype "passive"))
      (node (ref "R46") (pin "2") (pinfunction "2_2") (pintype "passive"))
    )
    (net (code "65") (name "Net-(Q18-S)") (class "Default")
      (node (ref "Q18") (pin "1") (pinfunction "S_1") (pintype "passive"))
      (node (ref "Q19") (pin "1") (pinfunction "S_1") (pintype "passive"))
      (node (ref "R50") (pin "2") (pinfunction "2_2") (pintype "passive"))
    )
    (net (code "66") (name "Net-(Q19-G)") (class "Default")
      (node (ref "C37") (pin "2") (pinfunction "2_2") (pintype "passive"))
      (node (ref "D11") (pin "A") (pinfunction "A_A") (pintype "passive"))
      (node (ref "D9") (pin "C") (pinfunction "C_C") (pintype "passive"))
      (node (ref "Q19") (pin "2") (pinfunction "G_2") (pintype "passive"))
      (node (ref "R47") (pin "2") (pinfunction "2_2") (pintype "passive"))
      (node (ref "VR3B") (pin "2") (pinfunction "2_2") (pintype "passive"))
      (node (ref "VR3B") (pin "3") (pinfunction "3_3") (pintype "passive"))
    )
    (net (code "67") (name "Net-(Q20-C)") (class "Default")
      (node (ref "C37") (pin "1") (pinfunction "1_1") (pintype "passive"))
      (node (ref "D10") (pin "A") (pinfunction "A_A") (pintype "passive"))
      (node (ref "D11") (pin "C") (pinfunction "C_C") (pintype "passive"))
      (node (ref "Q20") (pin "1") (pinfunction "C_1") (pintype "passive"))
      (node (ref "R48") (pin "1") (pinfunction "1_1") (pintype "passive"))
      (node (ref "R49") (pin "2") (pinfunction "2_2") (pintype "passive"))
      (node (ref "VR3B") (pin "1") (pinfunction "1_1") (pintype "passive"))
    )
    (net (code "68") (name "Net-(Q21-B)") (class "Default")
      (node (ref "Q21") (pin "1") (pinfunction "B_1") (pintype "passive"))
      (node (ref "R61") (pin "2") (pinfunction "2_2") (pintype "passive"))
    )
    (net (code "69") (name "Net-(Q21-C)") (class "Default")
      (node (ref "Q21") (pin "2") (pinfunction "C_2") (pintype "passive"))
      (node (ref "R56") (pin "1") (pinfunction "1_1") (pintype "passive"))
      (node (ref "R58") (pin "1") (pinfunction "1_1") (pintype "passive"))
    )
    (net (code "70") (name "Net-(R28-Pad2)") (class "Default")
      (node (ref "R28") (pin "2") (pinfunction "2_2") (pintype "passive"))
      (node (ref "RT1") (pin "1") (pinfunction "1_1") (pintype "passive"))
    )
    (net (code "71") (name "Net-(R29-Pad1)") (class "Default")
      (node (ref "R29") (pin "1") (pinfunction "1_1") (pintype "passive"))
      (node (ref "RT1") (pin "3") (pinfunction "3_3") (pintype "passive"))
    )
    (net (code "72") (name "Net-(R32-Pad2)") (class "Default")
      (node (ref "R32") (pin "2") (pinfunction "2_2") (pintype "passive"))
      (node (ref "R39") (pin "1") (pinfunction "1_1") (pintype "passive"))
      (node (ref "R43") (pin "1") (pinfunction "1_1") (pintype "passive"))
    )
    (net (code "73") (name "Net-(R62-Pad2)") (class "Default")
      (node (ref "R62") (pin "2") (pinfunction "2_2") (pintype "passive"))
      (node (ref "VR1") (pin "2") (pinfunction "2_2") (pintype "passive"))
    )
    (net (code "74") (name "Net-(SW1-P)") (class "Default")
      (node (ref "R59") (pin "2") (pinfunction "2_2") (pintype "passive"))
      (node (ref "R60") (pin "1") (pinfunction "1_1") (pintype "passive"))
      (node (ref "R61") (pin "1") (pinfunction "1_1") (pintype "passive"))
      (node (ref "SW1") (pin "2") (pinfunction "P_2") (pintype "passive"))
    )
    (net (code "75") (name "Net-(SW1-S)") (class "Default")
      (node (ref "R3") (pin "1") (pinfunction "1_1") (pintype "passive"))
      (node (ref "SW1") (pin "3") (pinfunction "S_3") (pintype "passive"))
    )
    (net (code "76") (name "Net-(SW2-P)") (class "Default")
      (node (ref "R55") (pin "2") (pinfunction "2_2") (pintype "passive"))
      (node (ref "SW2") (pin "1") (pinfunction "P_1") (pintype "passive"))
    )
    (net (code "77") (name "Net-(VR1-Pad3)") (class "Default")
      (node (ref "VR1") (pin "3") (pinfunction "3_3") (pintype "passive"))
      (node (ref "VR2") (pin "2") (pinfunction "2_2") (pintype "passive"))
    )
    (net (code "78") (name "VA") (class "Default")
      (node (ref "C5") (pin "+") (pinfunction "+_+") (pintype "passive"))
      (node (ref "Q1") (pin "3") (pinfunction "E_3") (pintype "passive"))
      (node (ref "Q19") (pin "3") (pinfunction "D_3") (pintype "passive"))
      (node (ref "Q2") (pin "2") (pinfunction "C_2") (pintype "passive"))
      (node (ref "Q20") (pin "3") (pinfunction "E_3") (pintype "passive"))
      (node (ref "Q5") (pin "3") (pinfunction "D_3") (pintype "passive"))
      (node (ref "Q6") (pin "2") (pinfunction "C_2") (pintype "passive"))
      (node (ref "R11") (pin "2") (pinfunction "2_2") (pintype "passive"))
      (node (ref "R17") (pin "2") (pinfunction "2_2") (pintype "passive"))
      (node (ref "R20") (pin "2") (pinfunction "2_2") (pintype "passive"))
      (node (ref "R23") (pin "2") (pinfunction "2_2") (pintype "passive"))
      (node (ref "R27") (pin "2") (pinfunction "2_2") (pintype "passive"))
      (node (ref "R3") (pin "2") (pinfunction "2_2") (pintype "passive"))
      (node (ref "R57") (pin "2") (pinfunction "2_2") (pintype "passive"))
      (node (ref "R58") (pin "2") (pinfunction "2_2") (pintype "passive"))
    )
    (net (code "79") (name "VB") (class "Default")
      (node (ref "C8") (pin "+") (pinfunction "+_+") (pintype "passive"))
      (node (ref "R10") (pin "1") (pinfunction "1_1") (pintype "passive"))
      (node (ref "R11") (pin "1") (pinfunction "1_1") (pintype "passive"))
      (node (ref "R12") (pin "1") (pinfunction "1_1") (pintype "passive"))
      (node (ref "R13") (pin "1") (pinfunction "1_1") (pintype "passive"))
      (node (ref "R15") (pin "1") (pinfunction "1_1") (pintype "passive"))
      (node (ref "R16") (pin "1") (pinfunction "1_1") (pintype "passive"))
      (node (ref "R18") (pin "1") (pinfunction "1_1") (pintype "passive"))
      (node (ref "R46") (pin "1") (pinfunction "1_1") (pintype "passive"))
      (node (ref "R51") (pin "1") (pinfunction "1_1") (pintype "passive"))
      (node (ref "R52") (pin "1") (pinfunction "1_1") (pintype "passive"))
      (node (ref "R54") (pin "1") (pinfunction "1_1") (pintype "passive"))
      (node (ref "R7") (pin "1") (pinfunction "1_1") (pintype "passive"))
      (node (ref "R9") (pin "2") (pinfunction "2_2") (pintype "passive"))
    )
    (net (code "80") (name "VC") (class "Default")
      (node (ref "C18") (pin "+") (pinfunction "+_+") (pintype "passive"))
      (node (ref "Q10") (pin "3") (pinfunction "D_3") (pintype "passive"))
      (node (ref "Q12") (pin "3") (pinfunction "E_3") (pintype "passive"))
      (node (ref "Q14") (pin "3") (pinfunction "D_3") (pintype "passive"))
      (node (ref "Q15") (pin "3") (pinfunction "E_3") (pintype "passive"))
      (node (ref "Q6") (pin "3") (pinfunction "E_3") (pintype "passive"))
      (node (ref "R29") (pin "2") (pinfunction "2_2") (pintype "passive"))
      (node (ref "R34") (pin "2") (pinfunction "2_2") (pintype "passive"))
      (node (ref "R44") (pin "2") (pinfunction "2_2") (pintype "passive"))
    )
    (net (code "81") (name "VD") (class "Default")
      (node (ref "C20") (pin "+") (pinfunction "+_+") (pintype "passive"))
      (node (ref "R33") (pin "1") (pinfunction "1_1") (pintype "passive"))
      (node (ref "R41") (pin "1") (pinfunction "1_1") (pintype "passive"))
      (node (ref "RT1") (pin "2") (pinfunction "2_2") (pintype "passive"))
    )
  )
)
